# CSI2-RPI-NANO_Rev01.net
KiCad netlist of a schematic drawn in Altium Designer
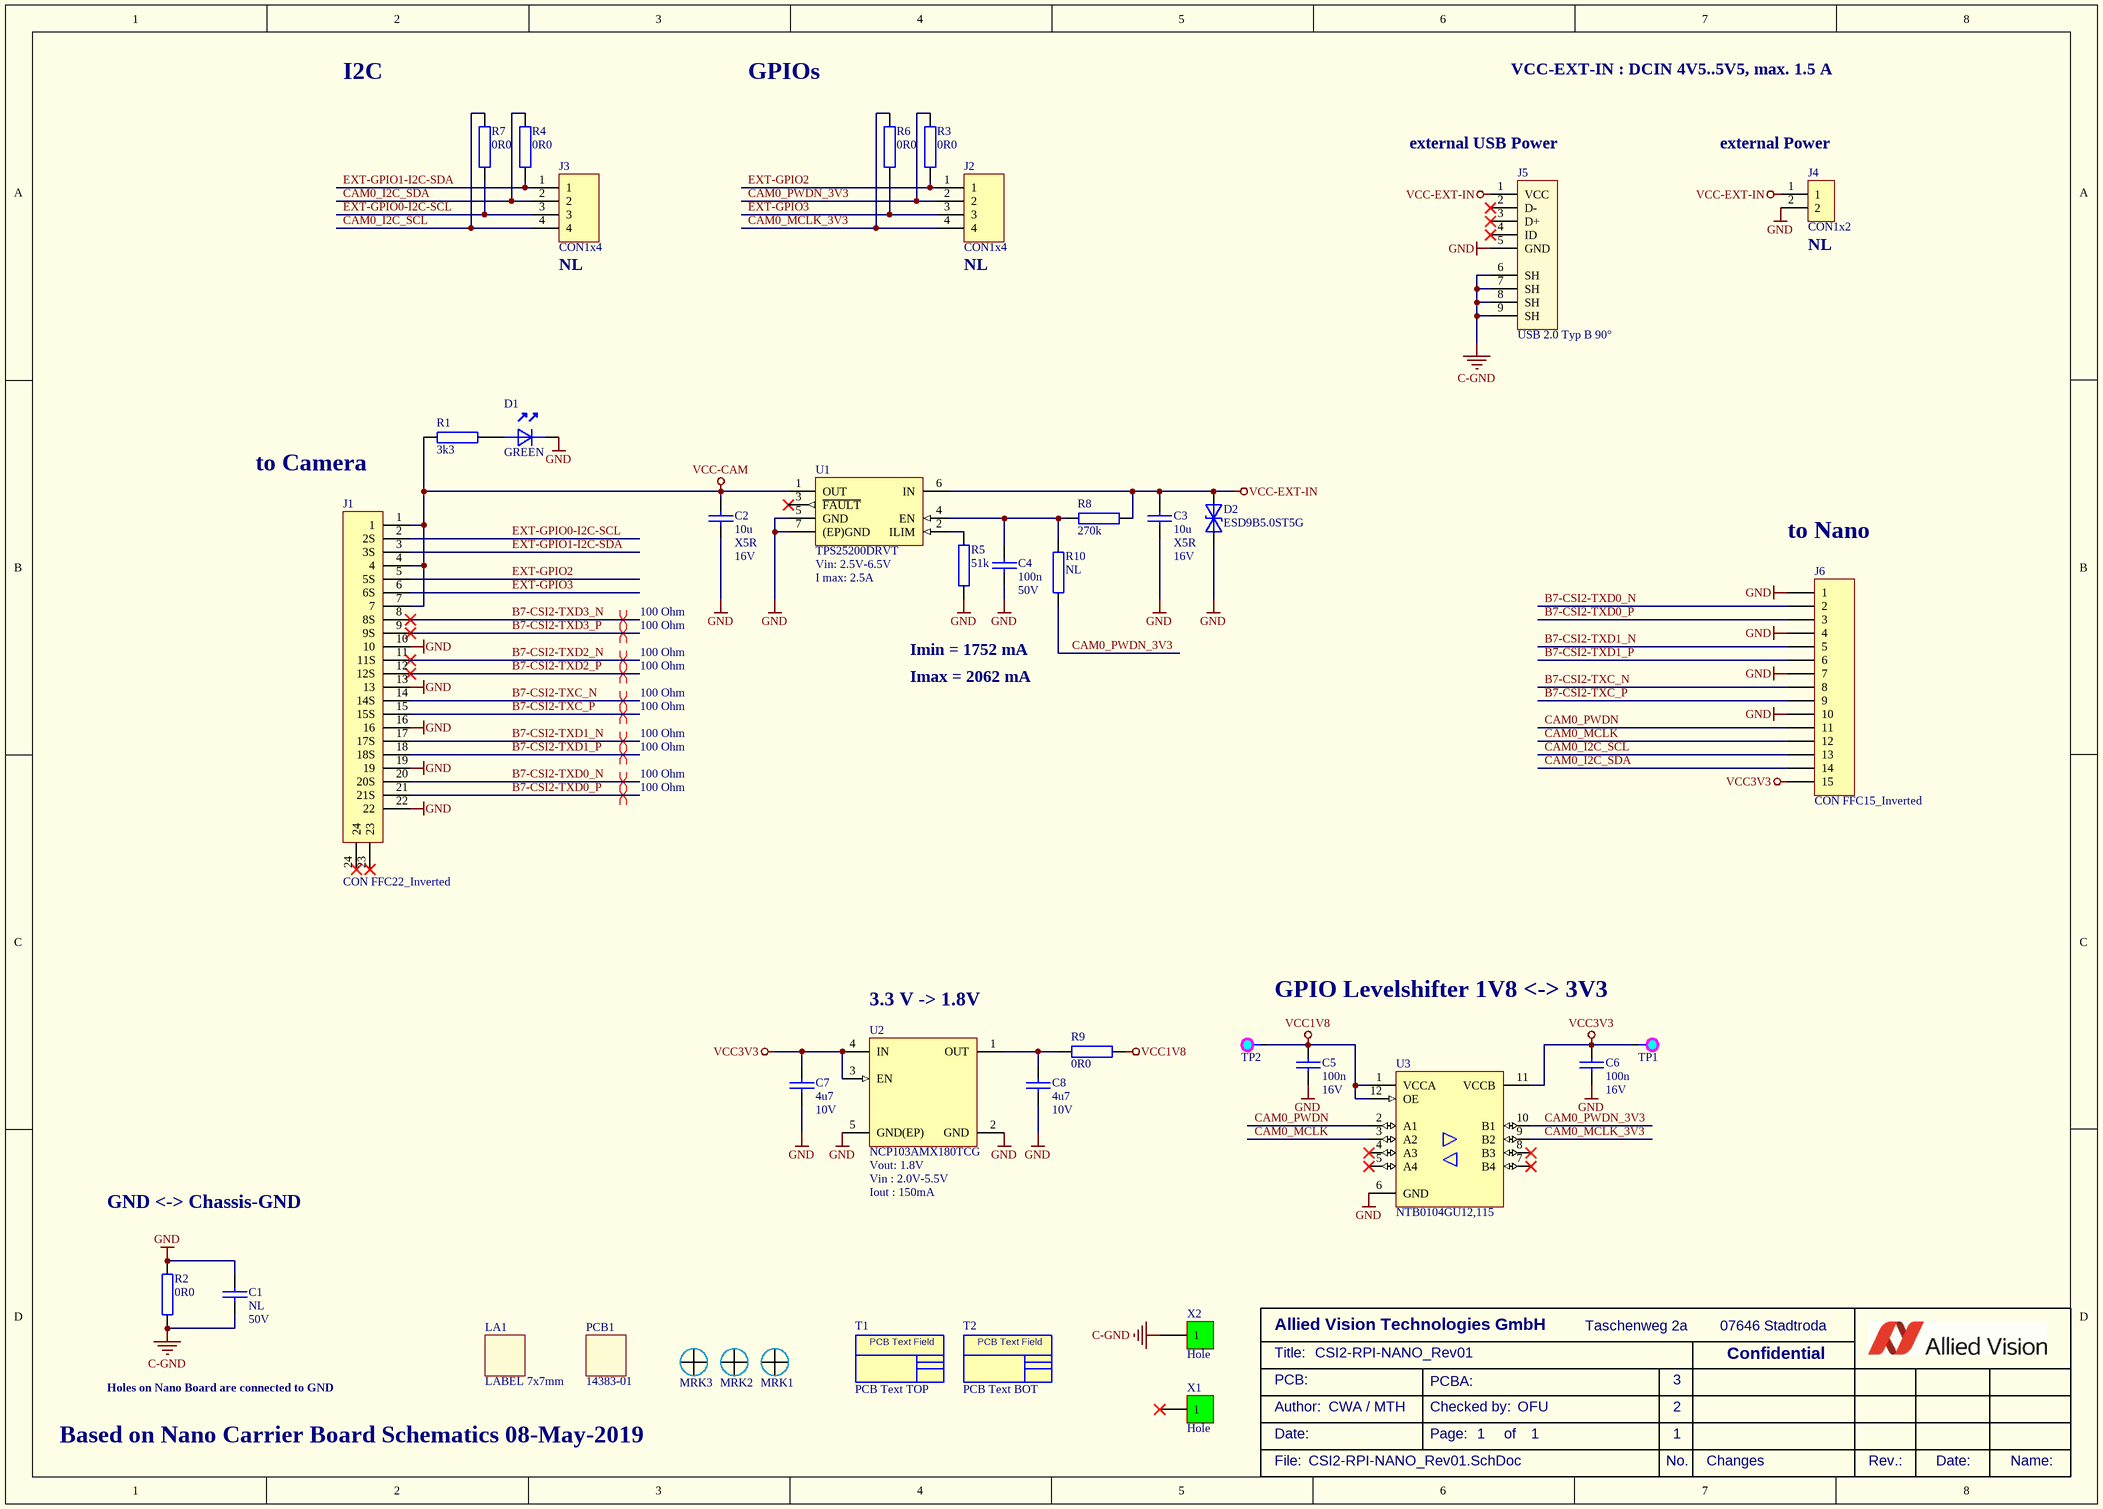
[diagram p0: CSI2-RPI-NANO_Rev01.SchDoc]

(export (version "E")
  (design (tool "Eeschema 10.0.6"))
  (components
    (comp (ref "C1")
      (value "NL")
      (footprint "C-0603_1.0")
      (description "Capacitor Ceramic SMD/0603/50V/X7R/10%")
      (fields
        (field (name "MANUFACTURER") "several")
        (field (name "TOLERANCE") "10%")
        (field (name "VOLTAGE") "50V")
      )
      (libsource (lib "AVT_KHK_Lib") (part "C X 0603"))
    )
    (comp (ref "C2")
      (value "10u")
      (footprint "C-0805_1.4")
      (description "Capacitor Ceramic SMD/0805/16V/X5R/10%")
      (fields
        (field (name "KHK PART NUMBER") "K8340151")
        (field (name "MANUFACTURER") "several")
        (field (name "DIELECTRIC") "X5R")
        (field (name "VOLTAGE") "16V")
      )
      (libsource (lib "AVT_KHK_Lib") (part "C 10U 16V X5R 0805"))
    )
    (comp (ref "C3")
      (value "10u")
      (footprint "C-0805_1.4")
      (description "Capacitor Ceramic SMD/0805/16V/X5R/10%")
      (fields
        (field (name "KHK PART NUMBER") "K8340151")
        (field (name "MANUFACTURER") "several")
        (field (name "DIELECTRIC") "X5R")
        (field (name "VOLTAGE") "16V")
      )
      (libsource (lib "AVT_KHK_Lib") (part "C 10U 16V X5R 0805"))
    )
    (comp (ref "C4")
      (value "100n")
      (footprint "C-0603_1.0")
      (description "Capacitor Ceramic SMD/0603/50V/X7R/10%")
      (fields
        (field (name "KHK PART NUMBER") "K8340023")
        (field (name "MANUFACTURER") "several")
        (field (name "VOLTAGE") "50V")
      )
      (libsource (lib "AVT_KHK_Lib") (part "C 100N 50V X7R 0603"))
    )
    (comp (ref "C5")
      (value "100n")
      (footprint "C-0402_0.55")
      (description "Capacitor Ceramic SMD/0402/16V/X7R/10%")
      (fields
        (field (name "KHK PART NUMBER") "K8340114")
        (field (name "MANUFACTURER") "several")
        (field (name "VOLTAGE") "16V")
      )
      (libsource (lib "AVT_KHK_Lib") (part "C 100N 10% 16V X7R 402"))
    )
    (comp (ref "C6")
      (value "100n")
      (footprint "C-0402_0.55")
      (description "Capacitor Ceramic SMD/0402/16V/X7R/10%")
      (fields
        (field (name "KHK PART NUMBER") "K8340114")
        (field (name "MANUFACTURER") "several")
        (field (name "VOLTAGE") "16V")
      )
      (libsource (lib "AVT_KHK_Lib") (part "C 100N 10% 16V X7R 402"))
    )
    (comp (ref "C7")
      (value "4u7")
      (footprint "C-0603_1.0")
      (description "Capacitor Ceramic SMD/0603/10V/X5R/10%")
      (fields
        (field (name "KHK PART NUMBER") "1431")
        (field (name "MANUFACTURER") "several")
        (field (name "VOLTAGE") "10V")
      )
      (libsource (lib "AVT_KHK_Lib") (part "C 4U7 10V X5R 0603"))
    )
    (comp (ref "C8")
      (value "4u7")
      (footprint "C-0603_1.0")
      (description "Capacitor Ceramic SMD/0603/10V/X5R/10%")
      (fields
        (field (name "KHK PART NUMBER") "1431")
        (field (name "MANUFACTURER") "several")
        (field (name "VOLTAGE") "10V")
      )
      (libsource (lib "AVT_KHK_Lib") (part "C 4U7 10V X5R 0603"))
    )
    (comp (ref "D1")
      (value "GREEN")
      (footprint "D-0603-LED")
      (description "Chip LED green 430mcd")
      (fields (field (name "KHK PART NUMBER") "8172") (field (name "MANUFACTURER") "Würth"))
      (libsource (lib "AVT_KHK_Lib") (part "D LED 0603 green"))
    )
    (comp (ref "D2")
      (value "ESD9B5.0ST5G")
      (footprint "D-SOD923")
      (description "DIODE TVS; 400W; 5.8-7.8V; BIDIRECT")
      (fields (field (name "KHK PART NUMBER") "7250") (field (name "MANUFACTURER") "ON Semiconductor"))
      (libsource (lib "AVT_KHK_Lib") (part "D ESD9B5.0ST5G"))
    )
    (comp (ref "J1")
      (value "CON FFC22_Inverted")
      (footprint "J-FH55-22S-0.5SH - Inverted Pins")
      (description "FFC Connector 0.5mm shielded")
      (fields
        (field (name "KHK PART NUMBER") "10357")
        (field (name "MANUFACTURER PART NUMBER") "FH55-22S-0.5SH")
      )
      (libsource (lib "AVT_KHK_Lib") (part "CON FFC22_FH55-22S-0.5SH_Inverted"))
    )
    (comp (ref "J2")
      (value "CON1x4")
      (footprint "CON 1x4 RM2.54")
      (description "Stiftleiste; 1x4; 2.54mm; gerade")
      (fields (field (name "MANUFACTURER") "Harwin") (field (name "MANUFACTURER PART NUMBER") "M20-999 0445"))
      (libsource (lib "AVT_KHK_Lib") (part "CON 1x4 2.54"))
    )
    (comp (ref "J3")
      (value "CON1x4")
      (footprint "CON 1x4 RM2.54")
      (description "Stiftleiste; 1x4; 2.54mm; gerade")
      (fields (field (name "MANUFACTURER") "Harwin") (field (name "MANUFACTURER PART NUMBER") "M20-999 0445"))
      (libsource (lib "AVT_KHK_Lib") (part "CON 1x4 2.54"))
    )
    (comp (ref "J4")
      (value "CON1x2")
      (footprint "CON 1x2 RM2.54")
      (description "Stiftleiste; 1x2; 2.54mm; gerade")
      (fields
        (field (name "MANUFACTURER") "fischer elektronik")
        (field (name "MANUFACTURER PART NUMBER") "SL 11 124 2 G")
      )
      (libsource (lib "AVT_KHK_Lib") (part "CON 1x2 2.54"))
    )
    (comp (ref "J5")
      (value "USB 2.0 Typ B 90°")
      (footprint "J-629105150521")
      (description "Micro USB 2.0 Typ B 90°")
      (fields (field (name "KHK PART NUMBER") "14360") (field (name "MANUFACTURER") "WE"))
      (libsource (lib "Connector") (part "CON USB 2.0 Typ B 90°"))
    )
    (comp (ref "J6")
      (value "CON FFC15_Inverted")
      (footprint "J-1-1734248-5 - Inverted Pins")
      (description "FFC Connector 1mm")
      (fields (field (name "MANUFACTURER PART NUMBER") "1-1734248-5") (field (name "MANUFACTURER") "TE"))
      (libsource (lib "AVT_KHK_Lib") (part "CON FFC15_1-1734248-5_Inverted"))
    )
    (comp (ref "LA1")
      (value "LABEL 7x7mm")
      (footprint "PCB LABEL 7x7")
      (fields (field (name "MANUFACTURER") "several"))
      (libsource (lib "Misc") (part "PCB LABEL 7x7"))
    )
    (comp (ref "MRK1")
      (value "Marker Single Layer")
      (footprint "PCB_Marker_Pad_top")
      (description "Position Marker for PCBs")
      (libsource (lib "AVT_KHK_Lib") (part "PCB Marker Pad Single Layer"))
    )
    (comp (ref "MRK2")
      (value "Marker Single Layer")
      (footprint "PCB_Marker_Pad_top")
      (description "Position Marker for PCBs")
      (libsource (lib "AVT_KHK_Lib") (part "PCB Marker Pad Single Layer"))
    )
    (comp (ref "MRK3")
      (value "Marker Single Layer")
      (footprint "PCB_Marker_Pad_top")
      (description "Position Marker for PCBs")
      (libsource (lib "AVT_KHK_Lib") (part "PCB Marker Pad Single Layer"))
    )
    (comp (ref "PCB1")
      (value "14383-01")
      (description "PCB ML04")
      (fields (field (name "KHK PART NUMBER") "14377-01") (field (name "MANUFACTURER") "several"))
      (libsource (lib "AVT_KHK_Lib") (part "PCB"))
    )
    (comp (ref "R1")
      (value "3k3")
      (footprint "R-0603_0.6")
      (description "Standard Resistor SMD/0603/1%/100mW/TK100")
      (fields (field (name "KHK PART NUMBER") "K8250070") (field (name "MANUFACTURER") "several"))
      (libsource (lib "AVT_KHK_Lib") (part "R 3K3 1% 0603"))
    )
    (comp (ref "R2")
      (value "0R0")
      (footprint "R-0603_0.6")
      (description "Standard Resistor SMD/0603/1%/100mW/TK200")
      (fields (field (name "KHK PART NUMBER") "K8250041") (field (name "MANUFACTURER") "several"))
      (libsource (lib "AVT_KHK_Lib") (part "R 0R0 1% 0603"))
    )
    (comp (ref "R3")
      (value "0R0")
      (footprint "R-0603_0.6")
      (description "Standard Resistor SMD/0603/1%/100mW/TK200")
      (fields (field (name "KHK PART NUMBER") "K8250041") (field (name "MANUFACTURER") "several"))
      (libsource (lib "AVT_KHK_Lib") (part "R 0R0 1% 0603"))
    )
    (comp (ref "R4")
      (value "0R0")
      (footprint "R-0603_0.6")
      (description "Standard Resistor SMD/0603/1%/100mW/TK100")
      (fields (field (name "KHK PART NUMBER") "K8250041") (field (name "MANUFACTURER") "several"))
      (libsource (lib "AVT_KHK_Lib") (part "R 0R0 1% 0603"))
    )
    (comp (ref "R5")
      (value "51k")
      (footprint "R-0603_0.6")
      (description "Standard Resistor SMD/0603/1%/100mW/TK100")
      (fields (field (name "KHK PART NUMBER") "K8250156") (field (name "MANUFACTURER") "several"))
      (libsource (lib "AVT_KHK_Lib") (part "R 51K 1% 0603"))
    )
    (comp (ref "R6")
      (value "0R0")
      (footprint "R-0603_0.6")
      (description "Standard Resistor SMD/0603/1%/100mW/TK200")
      (fields (field (name "KHK PART NUMBER") "K8250041") (field (name "MANUFACTURER") "several"))
      (libsource (lib "AVT_KHK_Lib") (part "R 0R0 1% 0603"))
    )
    (comp (ref "R7")
      (value "0R0")
      (footprint "R-0603_0.6")
      (description "Standard Resistor SMD/0603/1%/100mW/TK100")
      (fields (field (name "KHK PART NUMBER") "K8250041") (field (name "MANUFACTURER") "several"))
      (libsource (lib "AVT_KHK_Lib") (part "R 0R0 1% 0603"))
    )
    (comp (ref "R8")
      (value "270k")
      (footprint "R-0603_0.6")
      (description "Standard Resistor SMD/0603/1%/100mW/TK100")
      (fields (field (name "KHK PART NUMBER") "K8250170") (field (name "MANUFACTURER") "several"))
      (libsource (lib "AVT_KHK_Lib") (part "R 270K 1% 0603"))
    )
    (comp (ref "R9")
      (value "0R0")
      (footprint "R-0603_0.6")
      (description "Standard Resistor SMD/0603/1%/100mW/TK100")
      (fields (field (name "KHK PART NUMBER") "K8250041") (field (name "MANUFACTURER") "several"))
      (libsource (lib "Passive") (part "R 0R0 1% 0603"))
    )
    (comp (ref "R10")
      (value "NL")
      (footprint "R-0603_0.6")
      (description "Standard Resistor SMD/0603/1%/100mW/TK200")
      (fields (field (name "TOLERANCE") "1%"))
      (libsource (lib "AVT_KHK_Lib") (part "R X 0603"))
    )
    (comp (ref "T1")
      (value "PCB Text TOP")
      (footprint "PCB TEXTFIELD TOP 2")
      (description "PCB Textfield TOP")
      (libsource (lib "AVT_KHK_Lib") (part "PCB TEXT FIELD TOP"))
    )
    (comp (ref "T2")
      (value "PCB Text BOT")
      (footprint "PCB TEXTFIELD BOT 2")
      (description "PCB Textfield BOT")
      (libsource (lib "AVT_KHK_Lib") (part "PCB TEXT FIELD BOT"))
    )
    (comp (ref "TP1")
      (value "TP")
      (footprint "TP_16_10")
      (description "Testpoint: Pad=1,6mm; Hole=1,0mm")
      (libsource (lib "AVT_KHK_Lib") (part "TP_16_10"))
    )
    (comp (ref "TP2")
      (value "TP")
      (footprint "TP_16_10")
      (description "Testpoint: Pad=1,6mm; Hole=1,0mm")
      (libsource (lib "AVT_KHK_Lib") (part "TP_16_10"))
    )
    (comp (ref "U1")
      (value "TPS25200DRVT")
      (footprint "IC-DFN06_2.0x2.0x0.8")
      (description "IC/PWR/LOADSW;2V5-6V5;2A5;0R099/6-WDFN/2x2x0.8mm")
      (fields
        (field (name "KHK PART NUMBER") "14277")
        (field (name "MANUFACTURER") "Texas Instruments")
        (field (name "VIN") "2.5V-6.5V")
        (field (name "I MAX") "2.5A")
      )
      (libsource (lib "AVT_KHK_Lib") (part "IC  TPS25200DRVT"))
    )
    (comp (ref "U2")
      (value "NCP103AMX180TCG")
      (footprint "IC-XDFN4_1.0x1.0x0.6")
      (description "IC/PWR/LDO;2V0-5V5;1V8;0A150/uDFN4/1x1x0.6mm")
      (fields
        (field (name "KHK PART NUMBER") "14922")
        (field (name "MANUFACTURER") "ON Semi")
        (field (name "VOUT") "1.8V")
        (field (name "VIN") "Vin : 2.0V-5.5V")
        (field (name "IOUT") "Iout : 150mA")
      )
      (libsource (lib "AVT_KHK_Lib") (part "IC NCP103AMX180TCG"))
    )
    (comp (ref "U3")
      (value "NTB0104GU12,115")
      (footprint "IC-XQFN12_1.7x2x0.5")
      (description "IC/LOGIC/Levelshifter;Auto-Dir;Bidirectional;Push-Pull;-40-+125°C/")
      (fields (field (name "MANUFACTURER") "NXP") (field (name "KHK PART NUMBER") "14383"))
      (libsource (lib "AVT_KHK_Lib") (part "IC NTB0104GU12,115"))
    )
    (comp (ref "X1")
      (value "Hole")
      (footprint "HOLE-2.6-5.0-DK")
      (description "HOLE M2.5")
      (libsource (lib "AVT_KHK_Lib") (part "PCB HOLE M2.5-5-DK"))
    )
    (comp (ref "X2")
      (value "Hole")
      (footprint "HOLE-2.6-5.0-DK")
      (description "HOLE M2.5")
      (libsource (lib "AVT_KHK_Lib") (part "PCB HOLE M2.5-5-DK"))
    )
  )
  (nets
    (net (code "1") (name "/B7-CSI2-TXC_N") (class "Default")
      (node (ref "J1") (pin "14") (pinfunction "14S_14") (pintype "passive"))
      (node (ref "J6") (pin "8") (pinfunction "8_8") (pintype "passive"))
    )
    (net (code "2") (name "/B7-CSI2-TXC_P") (class "Default")
      (node (ref "J1") (pin "15") (pinfunction "15S_15") (pintype "passive"))
      (node (ref "J6") (pin "9") (pinfunction "9_9") (pintype "passive"))
    )
    (net (code "3") (name "/B7-CSI2-TXD0_N") (class "Default")
      (node (ref "J1") (pin "20") (pinfunction "20S_20") (pintype "passive"))
      (node (ref "J6") (pin "2") (pinfunction "2_2") (pintype "passive"))
    )
    (net (code "4") (name "/B7-CSI2-TXD0_P") (class "Default")
      (node (ref "J1") (pin "21") (pinfunction "21S_21") (pintype "passive"))
      (node (ref "J6") (pin "3") (pinfunction "3_3") (pintype "passive"))
    )
    (net (code "5") (name "/B7-CSI2-TXD1_N") (class "Default")
      (node (ref "J1") (pin "17") (pinfunction "17S_17") (pintype "passive"))
      (node (ref "J6") (pin "5") (pinfunction "5_5") (pintype "passive"))
    )
    (net (code "6") (name "/B7-CSI2-TXD1_P") (class "Default")
      (node (ref "J1") (pin "18") (pinfunction "18S_18") (pintype "passive"))
      (node (ref "J6") (pin "6") (pinfunction "6_6") (pintype "passive"))
    )
    (net (code "7") (name "/B7-CSI2-TXD2_N") (class "Default")
      (node (ref "J1") (pin "11") (pinfunction "11S_11") (pintype "passive+no_connect"))
    )
    (net (code "8") (name "/B7-CSI2-TXD2_P") (class "Default")
      (node (ref "J1") (pin "12") (pinfunction "12S_12") (pintype "passive+no_connect"))
    )
    (net (code "9") (name "/B7-CSI2-TXD3_N") (class "Default")
      (node (ref "J1") (pin "8") (pinfunction "8S_8") (pintype "passive+no_connect"))
    )
    (net (code "10") (name "/B7-CSI2-TXD3_P") (class "Default")
      (node (ref "J1") (pin "9") (pinfunction "9S_9") (pintype "passive+no_connect"))
    )
    (net (code "11") (name "/CAM0_I2C_SCL") (class "Default")
      (node (ref "J3") (pin "4") (pinfunction "4_4") (pintype "passive"))
      (node (ref "J6") (pin "13") (pinfunction "13_13") (pintype "passive"))
      (node (ref "R7") (pin "2") (pinfunction "2_2") (pintype "passive"))
    )
    (net (code "12") (name "/CAM0_I2C_SDA") (class "Default")
      (node (ref "J3") (pin "2") (pinfunction "2_2") (pintype "passive"))
      (node (ref "J6") (pin "14") (pinfunction "14_14") (pintype "passive"))
      (node (ref "R4") (pin "2") (pinfunction "2_2") (pintype "passive"))
    )
    (net (code "13") (name "/CAM0_MCLK") (class "Default")
      (node (ref "J6") (pin "12") (pinfunction "12_12") (pintype "passive"))
      (node (ref "U3") (pin "3") (pinfunction "A2_3") (pintype "bidirectional"))
    )
    (net (code "14") (name "/CAM0_MCLK_3V3") (class "Default")
      (node (ref "J2") (pin "4") (pinfunction "4_4") (pintype "passive"))
      (node (ref "R6") (pin "2") (pinfunction "2_2") (pintype "passive"))
      (node (ref "U3") (pin "9") (pinfunction "B2_9") (pintype "bidirectional"))
    )
    (net (code "15") (name "/CAM0_PWDN") (class "Default")
      (node (ref "J6") (pin "11") (pinfunction "11_11") (pintype "passive"))
      (node (ref "U3") (pin "2") (pinfunction "A1_2") (pintype "bidirectional"))
    )
    (net (code "16") (name "/CAM0_PWDN_3V3") (class "Default")
      (node (ref "J2") (pin "2") (pinfunction "2_2") (pintype "passive"))
      (node (ref "R10") (pin "1") (pinfunction "1_1") (pintype "passive"))
      (node (ref "R3") (pin "2") (pinfunction "2_2") (pintype "passive"))
      (node (ref "U3") (pin "10") (pinfunction "B1_10") (pintype "bidirectional"))
    )
    (net (code "17") (name "/EXT-GPIO0-I2C-SCL") (class "Default")
      (node (ref "J1") (pin "2") (pinfunction "2S_2") (pintype "passive"))
      (node (ref "J3") (pin "3") (pinfunction "3_3") (pintype "passive"))
      (node (ref "R7") (pin "1") (pinfunction "1_1") (pintype "passive"))
    )
    (net (code "18") (name "/EXT-GPIO1-I2C-SDA") (class "Default")
      (node (ref "J1") (pin "3") (pinfunction "3S_3") (pintype "passive"))
      (node (ref "J3") (pin "1") (pinfunction "1_1") (pintype "passive"))
      (node (ref "R4") (pin "1") (pinfunction "1_1") (pintype "passive"))
    )
    (net (code "19") (name "/EXT-GPIO2") (class "Default")
      (node (ref "J1") (pin "5") (pinfunction "5S_5") (pintype "passive"))
      (node (ref "J2") (pin "1") (pinfunction "1_1") (pintype "passive"))
      (node (ref "R3") (pin "1") (pinfunction "1_1") (pintype "passive"))
    )
    (net (code "20") (name "/EXT-GPIO3") (class "Default")
      (node (ref "J1") (pin "6") (pinfunction "6S_6") (pintype "passive"))
      (node (ref "J2") (pin "3") (pinfunction "3_3") (pintype "passive"))
      (node (ref "R6") (pin "1") (pinfunction "1_1") (pintype "passive"))
    )
    (net (code "21") (name "C-GND") (class "Default")
      (node (ref "C1") (pin "2") (pinfunction "2_2") (pintype "passive"))
      (node (ref "J5") (pin "6") (pinfunction "SH_6") (pintype "passive"))
      (node (ref "J5") (pin "7") (pinfunction "SH_7") (pintype "passive"))
      (node (ref "J5") (pin "8") (pinfunction "SH_8") (pintype "passive"))
      (node (ref "J5") (pin "9") (pinfunction "SH_9") (pintype "passive"))
      (node (ref "R2") (pin "1") (pinfunction "1_1") (pintype "passive"))
      (node (ref "X2") (pin "1") (pinfunction "1_1") (pintype "passive"))
    )
    (net (code "22") (name "GND") (class "Default")
      (node (ref "C1") (pin "1") (pinfunction "1_1") (pintype "passive"))
      (node (ref "C2") (pin "2") (pinfunction "2_2") (pintype "passive"))
      (node (ref "C3") (pin "2") (pinfunction "2_2") (pintype "passive"))
      (node (ref "C4") (pin "2") (pinfunction "2_2") (pintype "passive"))
      (node (ref "C5") (pin "2") (pinfunction "2_2") (pintype "passive"))
      (node (ref "C6") (pin "2") (pinfunction "2_2") (pintype "passive"))
      (node (ref "C7") (pin "2") (pinfunction "2_2") (pintype "passive"))
      (node (ref "C8") (pin "2") (pinfunction "2_2") (pintype "passive"))
      (node (ref "D1") (pin "K") (pinfunction "2_K") (pintype "passive"))
      (node (ref "D2") (pin "A") (pinfunction "A_A") (pintype "passive"))
      (node (ref "J1") (pin "10") (pinfunction "10_10") (pintype "passive"))
      (node (ref "J1") (pin "13") (pinfunction "13_13") (pintype "passive"))
      (node (ref "J1") (pin "16") (pinfunction "16_16") (pintype "passive"))
      (node (ref "J1") (pin "19") (pinfunction "19_19") (pintype "passive"))
      (node (ref "J1") (pin "22") (pinfunction "22_22") (pintype "passive"))
      (node (ref "J4") (pin "2") (pinfunction "2_2") (pintype "passive"))
      (node (ref "J5") (pin "5") (pinfunction "GND_5") (pintype "passive"))
      (node (ref "J6") (pin "1") (pinfunction "1_1") (pintype "passive"))
      (node (ref "J6") (pin "10") (pinfunction "10_10") (pintype "passive"))
      (node (ref "J6") (pin "4") (pinfunction "4_4") (pintype "passive"))
      (node (ref "J6") (pin "7") (pinfunction "7_7") (pintype "passive"))
      (node (ref "R2") (pin "2") (pinfunction "2_2") (pintype "passive"))
      (node (ref "R5") (pin "1") (pinfunction "1_1") (pintype "passive"))
      (node (ref "U1") (pin "5") (pinfunction "GND_5") (pintype "power_in"))
      (node (ref "U1") (pin "7") (pinfunction "(EP)GND_7") (pintype "power_in"))
      (node (ref "U2") (pin "2") (pinfunction "GND_2") (pintype "power_in"))
      (node (ref "U2") (pin "5") (pinfunction "GND(EP)_5") (pintype "power_in"))
      (node (ref "U3") (pin "6") (pinfunction "GND_6") (pintype "power_in"))
    )
    (net (code "23") (name "Net-(D1-1)") (class "Default")
      (node (ref "D1") (pin "A") (pinfunction "1_A") (pintype "passive"))
      (node (ref "R1") (pin "2") (pinfunction "2_2") (pintype "passive"))
    )
    (net (code "24") (name "Net-(U1-EN)") (class "Default")
      (node (ref "C4") (pin "1") (pinfunction "1_1") (pintype "passive"))
      (node (ref "R10") (pin "2") (pinfunction "2_2") (pintype "passive"))
      (node (ref "R8") (pin "1") (pinfunction "1_1") (pintype "passive"))
      (node (ref "U1") (pin "4") (pinfunction "EN_4") (pintype "input"))
    )
    (net (code "25") (name "Net-(U1-ILIM)") (class "Default")
      (node (ref "R5") (pin "2") (pinfunction "2_2") (pintype "passive"))
      (node (ref "U1") (pin "2") (pinfunction "ILIM_2") (pintype "input"))
    )
    (net (code "26") (name "Net-(U2-OUT)") (class "Default")
      (node (ref "C8") (pin "1") (pinfunction "1_1") (pintype "passive"))
      (node (ref "R9") (pin "1") (pinfunction "1_1") (pintype "passive"))
      (node (ref "U2") (pin "1") (pinfunction "OUT_1") (pintype "power_in"))
    )
    (net (code "27") (name "VCC-CAM") (class "Default")
      (node (ref "C2") (pin "1") (pinfunction "1_1") (pintype "passive"))
      (node (ref "J1") (pin "1") (pinfunction "1_1") (pintype "passive"))
      (node (ref "J1") (pin "4") (pinfunction "4_4") (pintype "passive"))
      (node (ref "J1") (pin "7") (pinfunction "7_7") (pintype "passive"))
      (node (ref "R1") (pin "1") (pinfunction "1_1") (pintype "passive"))
      (node (ref "U1") (pin "1") (pinfunction "OUT_1") (pintype "power_in"))
    )
    (net (code "28") (name "VCC-EXT-IN") (class "Default")
      (node (ref "C3") (pin "1") (pinfunction "1_1") (pintype "passive"))
      (node (ref "D2") (pin "K") (pinfunction "K_K") (pintype "passive"))
      (node (ref "J4") (pin "1") (pinfunction "1_1") (pintype "passive"))
      (node (ref "J5") (pin "1") (pinfunction "VCC_1") (pintype "passive"))
      (node (ref "R8") (pin "2") (pinfunction "2_2") (pintype "passive"))
      (node (ref "U1") (pin "6") (pinfunction "IN_6") (pintype "power_in"))
    )
    (net (code "29") (name "VCC1V8") (class "Default")
      (node (ref "C5") (pin "1") (pinfunction "1_1") (pintype "passive"))
      (node (ref "R9") (pin "2") (pinfunction "2_2") (pintype "passive"))
      (node (ref "TP2") (pin "1") (pinfunction "1_1") (pintype "passive"))
      (node (ref "U3") (pin "1") (pinfunction "VCCA_1") (pintype "power_in"))
      (node (ref "U3") (pin "12") (pinfunction "OE_12") (pintype "input"))
    )
    (net (code "30") (name "VCC3V3") (class "Default")
      (node (ref "C6") (pin "1") (pinfunction "1_1") (pintype "passive"))
      (node (ref "C7") (pin "1") (pinfunction "1_1") (pintype "passive"))
      (node (ref "J6") (pin "15") (pinfunction "15_15") (pintype "passive"))
      (node (ref "TP1") (pin "1") (pinfunction "1_1") (pintype "passive"))
      (node (ref "U2") (pin "3") (pinfunction "EN_3") (pintype "input"))
      (node (ref "U2") (pin "4") (pinfunction "IN_4") (pintype "power_in"))
      (node (ref "U3") (pin "11") (pinfunction "VCCB_11") (pintype "power_in"))
    )
    (net (code "31") (name "unconnected-(J1-Pad23)") (class "Default")
      (node (ref "J1") (pin "23") (pinfunction "23_23") (pintype "passive+no_connect"))
    )
    (net (code "32") (name "unconnected-(J1-Pad24)") (class "Default")
      (node (ref "J1") (pin "24") (pinfunction "24_24") (pintype "passive+no_connect"))
    )
    (net (code "33") (name "unconnected-(J5-D+-Pad3)") (class "Default")
      (node (ref "J5") (pin "3") (pinfunction "D+_3") (pintype "passive+no_connect"))
    )
    (net (code "34") (name "unconnected-(J5-D--Pad2)") (class "Default")
      (node (ref "J5") (pin "2") (pinfunction "D-_2") (pintype "passive+no_connect"))
    )
    (net (code "35") (name "unconnected-(J5-ID-Pad4)") (class "Default")
      (node (ref "J5") (pin "4") (pinfunction "ID_4") (pintype "passive+no_connect"))
    )
    (net (code "36") (name "unconnected-(U1-~{FAULT}-Pad3)") (class "Default")
      (node (ref "U1") (pin "3") (pinfunction "~{FAULT}_3") (pintype "output+no_connect"))
    )
    (net (code "37") (name "unconnected-(U3-A3-Pad4)") (class "Default")
      (node (ref "U3") (pin "4") (pinfunction "A3_4") (pintype "bidirectional+no_connect"))
    )
    (net (code "38") (name "unconnected-(U3-A4-Pad5)") (class "Default")
      (node (ref "U3") (pin "5") (pinfunction "A4_5") (pintype "bidirectional+no_connect"))
    )
    (net (code "39") (name "unconnected-(U3-B3-Pad8)") (class "Default")
      (node (ref "U3") (pin "8") (pinfunction "B3_8") (pintype "bidirectional+no_connect"))
    )
    (net (code "40") (name "unconnected-(U3-B4-Pad7)") (class "Default")
      (node (ref "U3") (pin "7") (pinfunction "B4_7") (pintype "bidirectional+no_connect"))
    )
    (net (code "41") (name "unconnected-(X1-Pad1)") (class "Default")
      (node (ref "X1") (pin "1") (pinfunction "1_1") (pintype "passive+no_connect"))
    )
  )
)
